# thermal.net
KiCad netlist of a schematic drawn in EAGLE
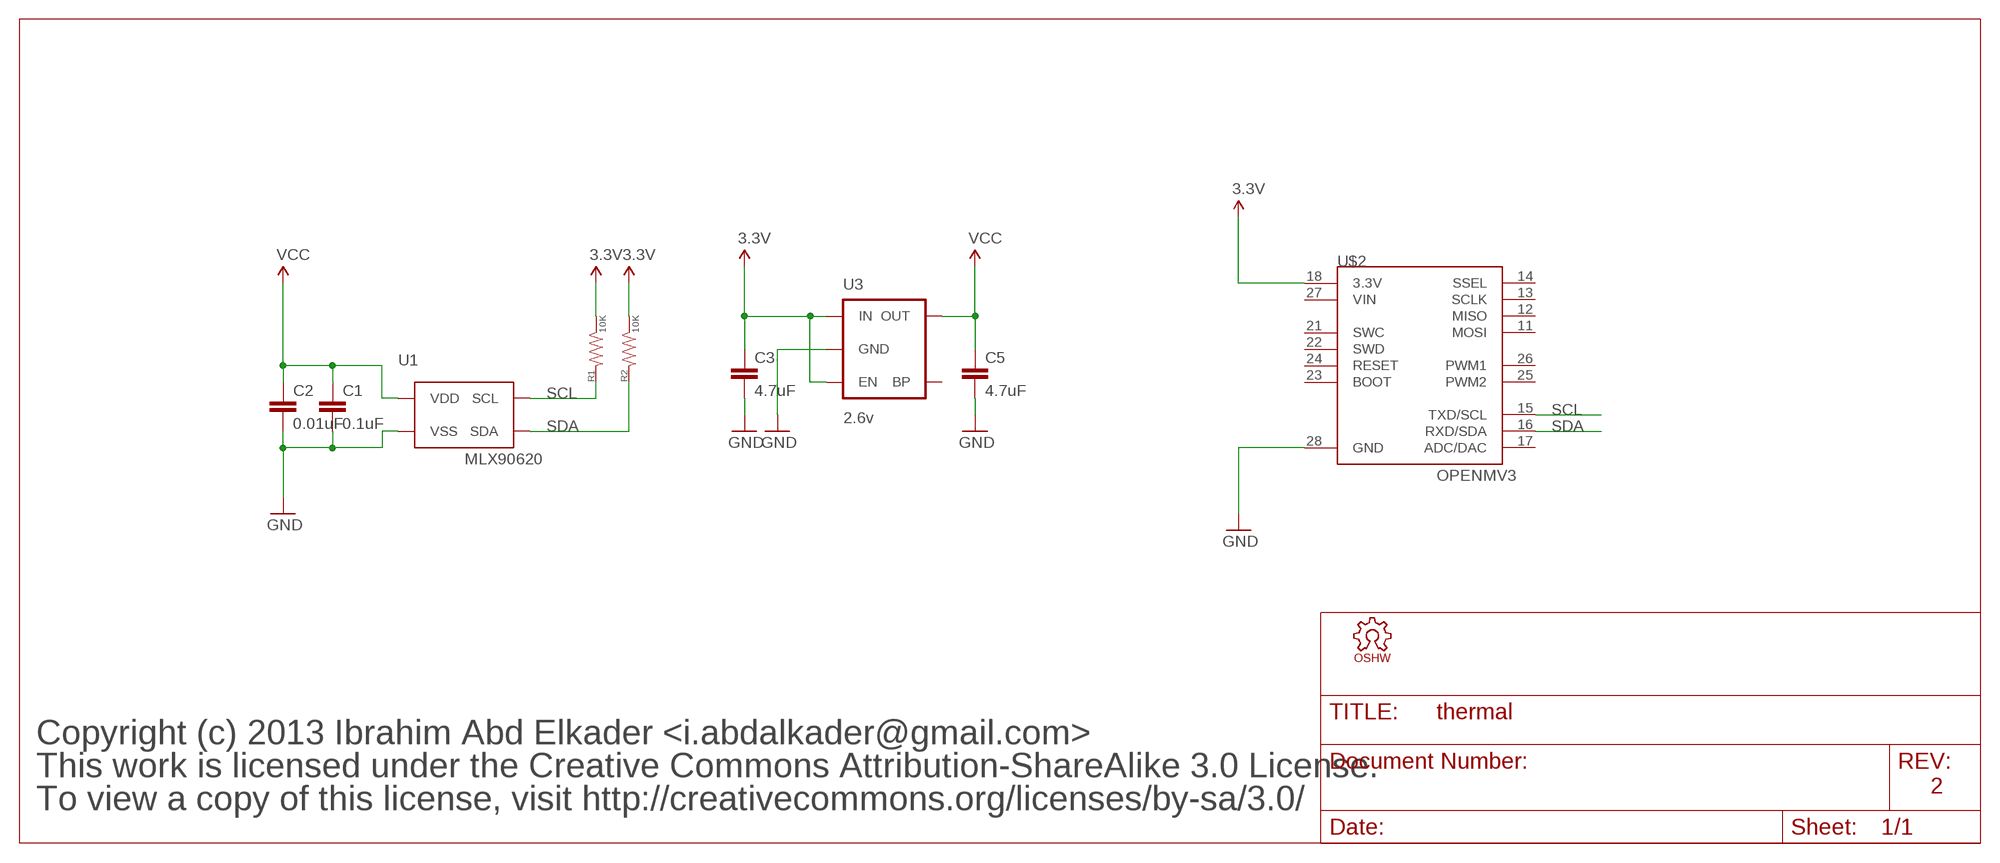
[diagram p0: schematic, sheet 1]

(export (version "E")
  (design (tool "Eeschema 10.0.6"))
  (components
    (comp (ref "C1")
      (value "0.1uF")
      (footprint "eagle-import:0603-CAP")
      (libsource (lib "eagle-import") (part "CAP0603-CAP"))
    )
    (comp (ref "C2")
      (value "0.01uF")
      (footprint "eagle-import:0603-CAP")
      (libsource (lib "eagle-import") (part "CAP0603-CAP"))
    )
    (comp (ref "C3")
      (value "4.7uF")
      (footprint "eagle-import:0603-CAP")
      (libsource (lib "eagle-import") (part "CAP0603-CAP"))
    )
    (comp (ref "C5")
      (value "4.7uF")
      (footprint "eagle-import:0603-CAP")
      (libsource (lib "eagle-import") (part "CAP0603-CAP"))
    )
    (comp (ref "LOGO1")
      (value "OSHW_LOGO_8MILX0150-NT")
      (footprint "eagle-import:OSHW_8X150_NOTEXT")
      (libsource (lib "eagle-import") (part "OSHW_LOGO_8MILX0150-NT"))
    )
    (comp (ref "R1")
      (value "10K")
      (footprint "eagle-import:0603-RES")
      (libsource (lib "eagle-import") (part "RESISTOR0603-RES"))
    )
    (comp (ref "R2")
      (value "10K")
      (footprint "eagle-import:0603-RES")
      (libsource (lib "eagle-import") (part "RESISTOR0603-RES"))
    )
    (comp (ref "U$2")
      (value "OPENMV3")
      (footprint "eagle-import:OPENMV3")
      (libsource (lib "eagle-import") (part "OPENMV3"))
    )
    (comp (ref "U1")
      (value "MLX90620")
      (footprint "eagle-import:TO39_4")
      (libsource (lib "eagle-import") (part "MLX90620"))
    )
    (comp (ref "U3")
      (value "2.6v")
      (footprint "eagle-import:SOT23-5")
      (libsource (lib "eagle-import") (part "V_REG_LDOSMD"))
    )
  )
  (nets
    (net (code "1") (name "/SCL") (class "Default")
      (node (ref "R1") (pin "2") (pinfunction "2_2") (pintype "passive"))
      (node (ref "U$2") (pin "15") (pinfunction "TXD/SCL_15") (pintype "bidirectional"))
      (node (ref "U1") (pin "1") (pinfunction "SCL_1") (pintype "bidirectional"))
    )
    (net (code "2") (name "/SDA") (class "Default")
      (node (ref "R2") (pin "2") (pinfunction "2_2") (pintype "passive"))
      (node (ref "U$2") (pin "16") (pinfunction "RXD/SDA_16") (pintype "bidirectional"))
      (node (ref "U1") (pin "2") (pinfunction "SDA_2") (pintype "bidirectional"))
    )
    (net (code "3") (name "/VIN") (class "Default")
      (node (ref "U$2") (pin "27") (pinfunction "VIN_27") (pintype "power_in"))
    )
    (net (code "4") (name "3.3V") (class "Default")
      (node (ref "C3") (pin "1") (pinfunction "1_1") (pintype "passive"))
      (node (ref "R1") (pin "1") (pinfunction "1_1") (pintype "passive"))
      (node (ref "R2") (pin "1") (pinfunction "1_1") (pintype "passive"))
      (node (ref "U$2") (pin "18") (pinfunction "3.3V_18") (pintype "power_in"))
      (node (ref "U3") (pin "1") (pinfunction "IN_1") (pintype "input"))
      (node (ref "U3") (pin "3") (pinfunction "EN_3") (pintype "input"))
    )
    (net (code "5") (name "GND") (class "Default")
      (node (ref "C1") (pin "2") (pinfunction "2_2") (pintype "passive"))
      (node (ref "C2") (pin "2") (pinfunction "2_2") (pintype "passive"))
      (node (ref "C3") (pin "2") (pinfunction "2_2") (pintype "passive"))
      (node (ref "C5") (pin "2") (pinfunction "2_2") (pintype "passive"))
      (node (ref "U$2") (pin "28") (pinfunction "GND_28") (pintype "power_in"))
      (node (ref "U1") (pin "4") (pinfunction "VSS_4") (pintype "power_in"))
      (node (ref "U3") (pin "2") (pinfunction "GND_2") (pintype "input"))
    )
    (net (code "6") (name "VCC") (class "Default")
      (node (ref "C1") (pin "1") (pinfunction "1_1") (pintype "passive"))
      (node (ref "C2") (pin "1") (pinfunction "1_1") (pintype "passive"))
      (node (ref "C5") (pin "1") (pinfunction "1_1") (pintype "passive"))
      (node (ref "U1") (pin "3") (pinfunction "VDD_3") (pintype "power_in"))
      (node (ref "U3") (pin "5") (pinfunction "OUT_5") (pintype "passive"))
    )
    (net (code "7") (name "unconnected-(U$2-ADC{slash}DAC-Pad17)") (class "Default")
      (node (ref "U$2") (pin "17") (pinfunction "ADC/DAC_17") (pintype "bidirectional"))
    )
    (net (code "8") (name "unconnected-(U$2-BOOT-Pad23)") (class "Default")
      (node (ref "U$2") (pin "23") (pinfunction "BOOT_23") (pintype "bidirectional"))
    )
    (net (code "9") (name "unconnected-(U$2-MISO-Pad12)") (class "Default")
      (node (ref "U$2") (pin "12") (pinfunction "MISO_12") (pintype "bidirectional"))
    )
    (net (code "10") (name "unconnected-(U$2-MOSI-Pad11)") (class "Default")
      (node (ref "U$2") (pin "11") (pinfunction "MOSI_11") (pintype "bidirectional"))
    )
    (net (code "11") (name "unconnected-(U$2-PWM1-Pad26)") (class "Default")
      (node (ref "U$2") (pin "26") (pinfunction "PWM1_26") (pintype "bidirectional"))
    )
    (net (code "12") (name "unconnected-(U$2-PWM2-Pad25)") (class "Default")
      (node (ref "U$2") (pin "25") (pinfunction "PWM2_25") (pintype "bidirectional"))
    )
    (net (code "13") (name "unconnected-(U$2-RESET-Pad24)") (class "Default")
      (node (ref "U$2") (pin "24") (pinfunction "RESET_24") (pintype "bidirectional"))
    )
    (net (code "14") (name "unconnected-(U$2-SCLK-Pad13)") (class "Default")
      (node (ref "U$2") (pin "13") (pinfunction "SCLK_13") (pintype "bidirectional"))
    )
    (net (code "15") (name "unconnected-(U$2-SSEL-Pad14)") (class "Default")
      (node (ref "U$2") (pin "14") (pinfunction "SSEL_14") (pintype "bidirectional"))
    )
    (net (code "16") (name "unconnected-(U$2-SWC-Pad21)") (class "Default")
      (node (ref "U$2") (pin "21") (pinfunction "SWC_21") (pintype "bidirectional"))
    )
    (net (code "17") (name "unconnected-(U$2-SWD-Pad22)") (class "Default")
      (node (ref "U$2") (pin "22") (pinfunction "SWD_22") (pintype "bidirectional"))
    )
    (net (code "18") (name "unconnected-(U3-BP-Pad4)") (class "Default")
      (node (ref "U3") (pin "4") (pinfunction "BP_4") (pintype "input"))
    )
  )
)
